# RS232-MITM.net
KiCad netlist of a schematic drawn in Altium Designer
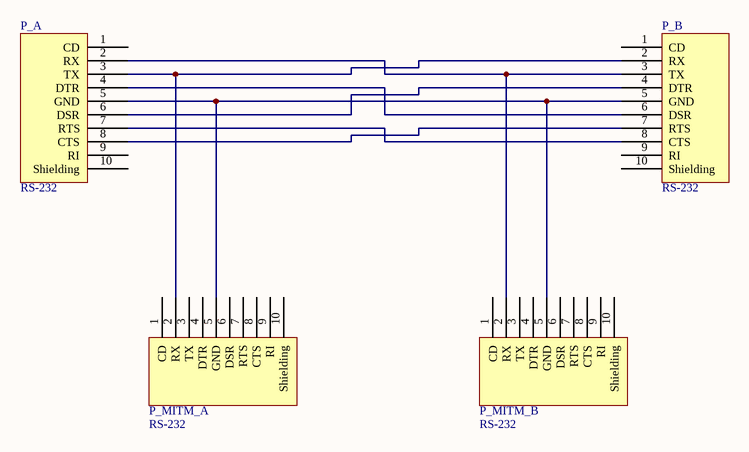
[diagram p0: RS232-MITM.SchDoc]

(export (version "E")
  (design (tool "Eeschema 10.0.6"))
  (components
    (comp (ref "P_A") (value "RS-232") (footprint "RS-232") (libsource (lib "") (part "RS-232_2")))
    (comp (ref "P_B") (value "RS-232") (footprint "RS-232") (libsource (lib "RS232-MITM") (part "RS-232")))
    (comp (ref "P_MITM_A")
      (value "RS-232")
      (footprint "RS-232 mirrored")
      (libsource (lib "") (part "RS-232_1"))
    )
    (comp (ref "P_MITM_B")
      (value "RS-232")
      (footprint "RS-232 mirrored")
      (libsource (lib "") (part "RS-232_1"))
    )
  )
  (nets
    (net (code "1") (name "Net-(P_A-CTS)") (class "Default")
      (node (ref "P_A") (pin "8") (pinfunction "CTS_8") (pintype "passive"))
      (node (ref "P_B") (pin "7") (pinfunction "RTS_7") (pintype "passive"))
    )
    (net (code "2") (name "Net-(P_A-DSR)") (class "Default")
      (node (ref "P_A") (pin "6") (pinfunction "DSR_6") (pintype "passive"))
      (node (ref "P_B") (pin "4") (pinfunction "DTR_4") (pintype "passive"))
    )
    (net (code "3") (name "Net-(P_A-DTR)") (class "Default")
      (node (ref "P_A") (pin "4") (pinfunction "DTR_4") (pintype "passive"))
      (node (ref "P_B") (pin "6") (pinfunction "DSR_6") (pintype "passive"))
    )
    (net (code "4") (name "Net-(P_A-GND)") (class "Default")
      (node (ref "P_A") (pin "5") (pinfunction "GND_5") (pintype "passive"))
      (node (ref "P_B") (pin "5") (pinfunction "GND_5") (pintype "passive"))
      (node (ref "P_MITM_A") (pin "5") (pinfunction "GND_5") (pintype "passive"))
      (node (ref "P_MITM_B") (pin "5") (pinfunction "GND_5") (pintype "passive"))
    )
    (net (code "5") (name "Net-(P_A-RTS)") (class "Default")
      (node (ref "P_A") (pin "7") (pinfunction "RTS_7") (pintype "passive"))
      (node (ref "P_B") (pin "8") (pinfunction "CTS_8") (pintype "passive"))
    )
    (net (code "6") (name "Net-(P_A-RX)") (class "Default")
      (node (ref "P_A") (pin "2") (pinfunction "RX_2") (pintype "passive"))
      (node (ref "P_B") (pin "3") (pinfunction "TX_3") (pintype "passive"))
      (node (ref "P_MITM_B") (pin "2") (pinfunction "RX_2") (pintype "passive"))
    )
    (net (code "7") (name "Net-(P_A-TX)") (class "Default")
      (node (ref "P_A") (pin "3") (pinfunction "TX_3") (pintype "passive"))
      (node (ref "P_B") (pin "2") (pinfunction "RX_2") (pintype "passive"))
      (node (ref "P_MITM_A") (pin "2") (pinfunction "RX_2") (pintype "passive"))
    )
    (net (code "8") (name "unconnected-(P_A-CD-Pad1)") (class "Default")
      (node (ref "P_A") (pin "1") (pinfunction "CD_1") (pintype "passive"))
    )
    (net (code "9") (name "unconnected-(P_A-RI-Pad9)") (class "Default")
      (node (ref "P_A") (pin "9") (pinfunction "RI_9") (pintype "passive"))
    )
    (net (code "10") (name "unconnected-(P_A-Shielding-Pad10)") (class "Default")
      (node (ref "P_A") (pin "10") (pinfunction "Shielding_10") (pintype "passive"))
    )
    (net (code "11") (name "unconnected-(P_B-CD-Pad1)") (class "Default")
      (node (ref "P_B") (pin "1") (pinfunction "CD_1") (pintype "passive"))
    )
    (net (code "12") (name "unconnected-(P_B-RI-Pad9)") (class "Default")
      (node (ref "P_B") (pin "9") (pinfunction "RI_9") (pintype "passive"))
    )
    (net (code "13") (name "unconnected-(P_B-Shielding-Pad10)") (class "Default")
      (node (ref "P_B") (pin "10") (pinfunction "Shielding_10") (pintype "passive"))
    )
    (net (code "14") (name "unconnected-(P_MITM_A-CD-Pad1)") (class "Default")
      (node (ref "P_MITM_A") (pin "1") (pinfunction "CD_1") (pintype "passive"))
    )
    (net (code "15") (name "unconnected-(P_MITM_A-CTS-Pad8)") (class "Default")
      (node (ref "P_MITM_A") (pin "8") (pinfunction "CTS_8") (pintype "passive"))
    )
    (net (code "16") (name "unconnected-(P_MITM_A-DSR-Pad6)") (class "Default")
      (node (ref "P_MITM_A") (pin "6") (pinfunction "DSR_6") (pintype "passive"))
    )
    (net (code "17") (name "unconnected-(P_MITM_A-DTR-Pad4)") (class "Default")
      (node (ref "P_MITM_A") (pin "4") (pinfunction "DTR_4") (pintype "passive"))
    )
    (net (code "18") (name "unconnected-(P_MITM_A-RI-Pad9)") (class "Default")
      (node (ref "P_MITM_A") (pin "9") (pinfunction "RI_9") (pintype "passive"))
    )
    (net (code "19") (name "unconnected-(P_MITM_A-RTS-Pad7)") (class "Default")
      (node (ref "P_MITM_A") (pin "7") (pinfunction "RTS_7") (pintype "passive"))
    )
    (net (code "20") (name "unconnected-(P_MITM_A-Shielding-Pad10)") (class "Default")
      (node (ref "P_MITM_A") (pin "10") (pinfunction "Shielding_10") (pintype "passive"))
    )
    (net (code "21") (name "unconnected-(P_MITM_A-TX-Pad3)") (class "Default")
      (node (ref "P_MITM_A") (pin "3") (pinfunction "TX_3") (pintype "passive"))
    )
    (net (code "22") (name "unconnected-(P_MITM_B-CD-Pad1)") (class "Default")
      (node (ref "P_MITM_B") (pin "1") (pinfunction "CD_1") (pintype "passive"))
    )
    (net (code "23") (name "unconnected-(P_MITM_B-CTS-Pad8)") (class "Default")
      (node (ref "P_MITM_B") (pin "8") (pinfunction "CTS_8") (pintype "passive"))
    )
    (net (code "24") (name "unconnected-(P_MITM_B-DSR-Pad6)") (class "Default")
      (node (ref "P_MITM_B") (pin "6") (pinfunction "DSR_6") (pintype "passive"))
    )
    (net (code "25") (name "unconnected-(P_MITM_B-DTR-Pad4)") (class "Default")
      (node (ref "P_MITM_B") (pin "4") (pinfunction "DTR_4") (pintype "passive"))
    )
    (net (code "26") (name "unconnected-(P_MITM_B-RI-Pad9)") (class "Default")
      (node (ref "P_MITM_B") (pin "9") (pinfunction "RI_9") (pintype "passive"))
    )
    (net (code "27") (name "unconnected-(P_MITM_B-RTS-Pad7)") (class "Default")
      (node (ref "P_MITM_B") (pin "7") (pinfunction "RTS_7") (pintype "passive"))
    )
    (net (code "28") (name "unconnected-(P_MITM_B-Shielding-Pad10)") (class "Default")
      (node (ref "P_MITM_B") (pin "10") (pinfunction "Shielding_10") (pintype "passive"))
    )
    (net (code "29") (name "unconnected-(P_MITM_B-TX-Pad3)") (class "Default")
      (node (ref "P_MITM_B") (pin "3") (pinfunction "TX_3") (pintype "passive"))
    )
  )
)
